# Arduino_MITCH_PCB.net
KiCad netlist of a schematic drawn in EAGLE
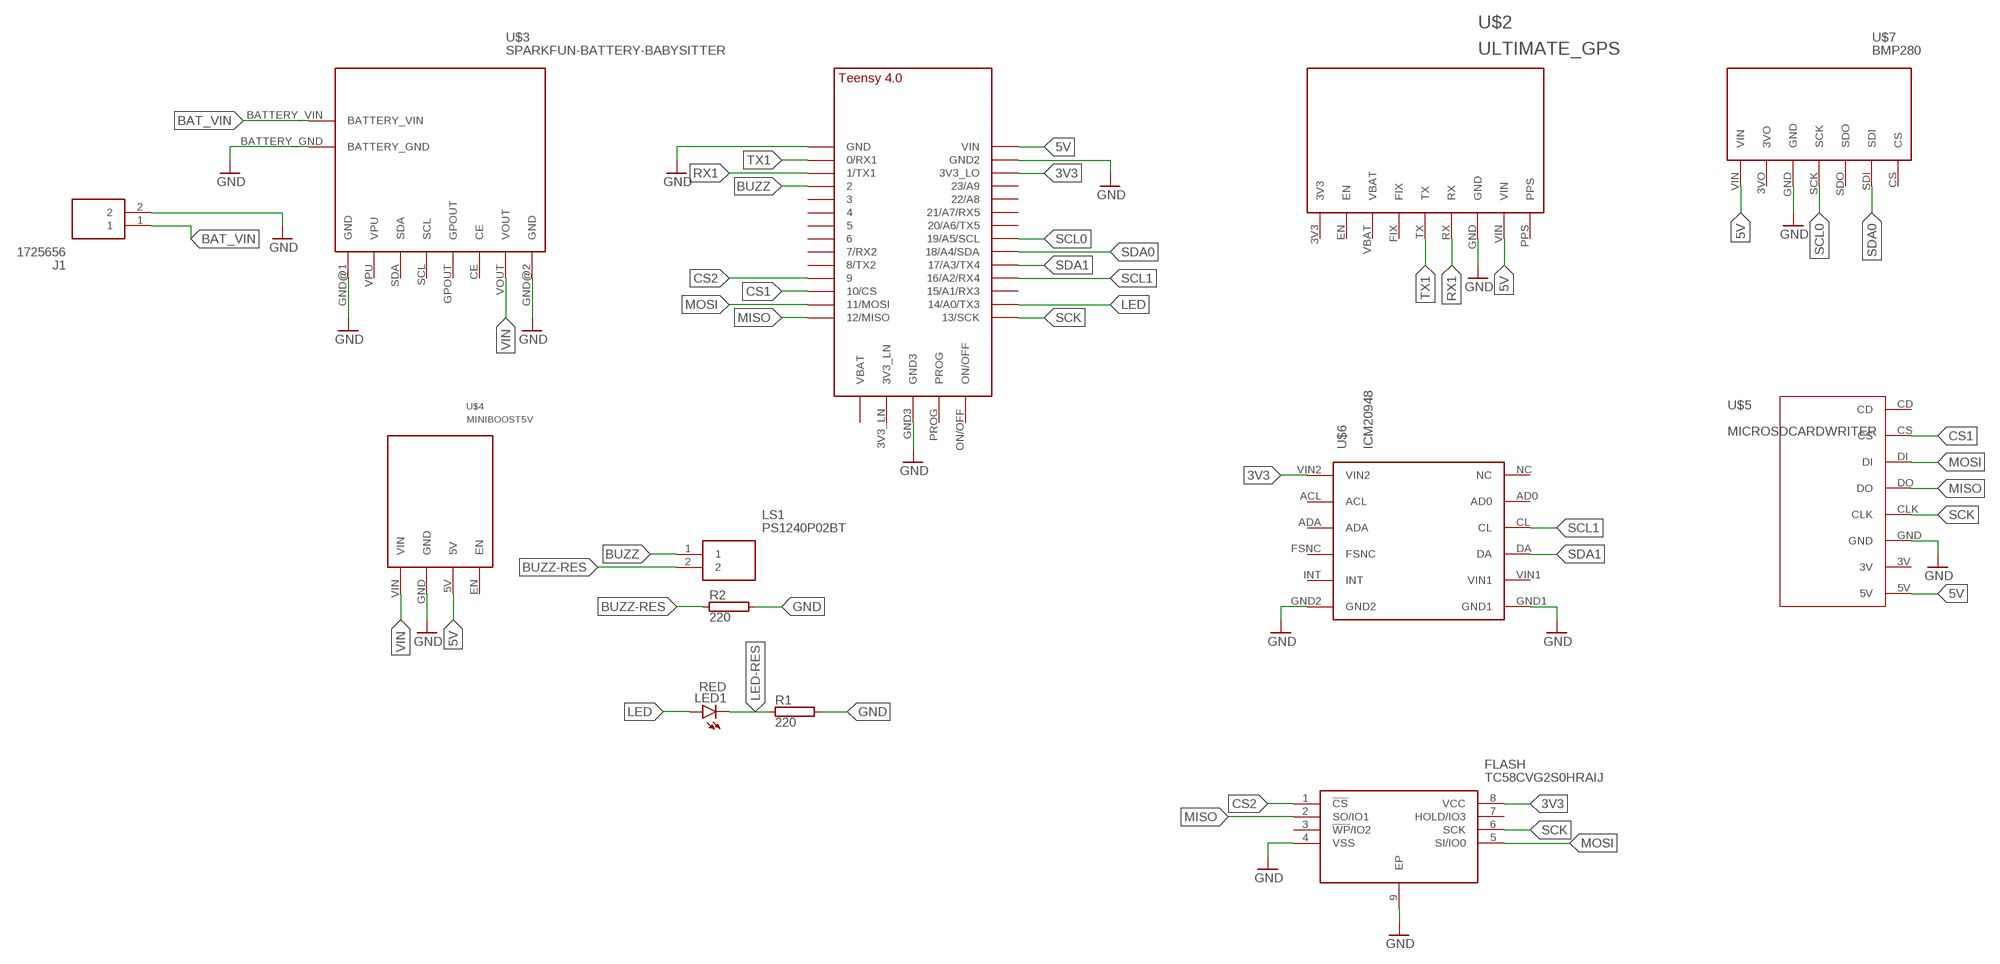
[diagram p0: schematic, sheet 1]

(export (version "E")
  (design (tool "Eeschema 10.0.6"))
  (components
    (comp (ref "FLASH")
      (value "TC58CVG2S0HRAIJ")
      (footprint "eagle-import:SON127P800X600X80-9N")
      (fields (field (name "MOUSER_PART_NUMBER") "757-TC58CVG2S0HRAIJ"))
      (libsource (lib "eagle-import") (part "TC58CVG2S0HRAIJ"))
    )
    (comp (ref "J1")
      (value "1725656")
      (footprint "eagle-import:1725656")
      (fields (field (name "MOUSER_PART_NUMBER") "651-1725656"))
      (libsource (lib "eagle-import") (part "1725656"))
    )
    (comp (ref "LED1")
      (value "RED")
      (footprint "eagle-import:LED5MM")
      (libsource (lib "eagle-import") (part "LED5MM"))
    )
    (comp (ref "LS1")
      (value "PS1240P02BT")
      (footprint "eagle-import:PS1240P02BT")
      (fields (field (name "MOUSER_PART_NUMBER") "810-PS1240P02BT"))
      (libsource (lib "eagle-import") (part "PS1240P02BT"))
    )
    (comp (ref "R1")
      (value "220")
      (footprint "eagle-import:HPS58")
      (libsource (lib "eagle-import") (part "RHPS58"))
    )
    (comp (ref "R2")
      (value "220")
      (footprint "eagle-import:HPS58")
      (libsource (lib "eagle-import") (part "RHPS58"))
    )
    (comp (ref "U$1")
      (value "TEENSY_4.0-BASIC")
      (footprint "eagle-import:TEENSY_4.0-BASIC")
      (libsource (lib "eagle-import") (part "TEENSY_4.0-BASIC"))
    )
    (comp (ref "U$2")
      (value "ULTIMATE_GPS")
      (footprint "eagle-import:ULTIMATE_GPS")
      (libsource (lib "eagle-import") (part "ULTIMATE_GPS"))
    )
    (comp (ref "U$3")
      (value "SPARKFUN-BATTERY-BABYSITTER")
      (footprint "eagle-import:SPARKFUN-BATTERY-BABYSITTER")
      (libsource (lib "eagle-import") (part "SPARKFUN-BATTERY-BABYSITTER"))
    )
    (comp (ref "U$4")
      (value "MINIBOOST5V")
      (footprint "eagle-import:MINIBOOST5V")
      (libsource (lib "eagle-import") (part "MINIBOOST5V"))
    )
    (comp (ref "U$5")
      (value "MICROSDCARDWRITER")
      (footprint "eagle-import:MICROSDCARDWRITER")
      (libsource (lib "eagle-import") (part "MICROSDCARDWRITER"))
    )
    (comp (ref "U$6")
      (value "ICM20948")
      (footprint "eagle-import:ICM20948")
      (libsource (lib "eagle-import") (part "ICM20948"))
    )
    (comp (ref "U$7")
      (value "BMP280")
      (footprint "eagle-import:BMP280")
      (libsource (lib "eagle-import") (part "BMP280"))
    )
  )
  (nets
    (net (code "1") (name "3V3") (class "Default")
      (node (ref "FLASH") (pin "8") (pinfunction "VCC_8") (pintype "bidirectional"))
      (node (ref "U$1") (pin "3V3_LO") (pinfunction "3V3_LO_3V3_LO") (pintype "bidirectional"))
      (node (ref "U$6") (pin "VIN2") (pinfunction "VIN2_VIN2") (pintype "bidirectional"))
    )
    (net (code "2") (name "5V") (class "Default")
      (node (ref "U$1") (pin "VIN") (pinfunction "VIN_VIN") (pintype "bidirectional"))
      (node (ref "U$2") (pin "VIN") (pinfunction "VIN_VIN") (pintype "bidirectional"))
      (node (ref "U$4") (pin "5V") (pinfunction "5V_5V") (pintype "bidirectional"))
      (node (ref "U$5") (pin "5V") (pinfunction "5V_5V") (pintype "bidirectional"))
      (node (ref "U$7") (pin "VIN") (pinfunction "VIN_VIN") (pintype "bidirectional"))
    )
    (net (code "3") (name "BAT_VIN") (class "Default")
      (node (ref "J1") (pin "1") (pinfunction "1_1") (pintype "bidirectional"))
      (node (ref "U$3") (pin "BATTERY_VIN") (pinfunction "BATTERY_VIN_BATTERY_VIN") (pintype "bidirectional"))
    )
    (net (code "4") (name "BUZZ") (class "Default")
      (node (ref "LS1") (pin "1") (pinfunction "1_1") (pintype "bidirectional"))
      (node (ref "U$1") (pin "2") (pinfunction "2_2") (pintype "bidirectional"))
    )
    (net (code "5") (name "BUZZ-RES") (class "Default")
      (node (ref "LS1") (pin "2") (pinfunction "2_2") (pintype "bidirectional"))
      (node (ref "R2") (pin "1") (pinfunction "1_1") (pintype "passive"))
    )
    (net (code "6") (name "CS1") (class "Default")
      (node (ref "U$1") (pin "10/CS") (pinfunction "10/CS_10/CS") (pintype "bidirectional"))
      (node (ref "U$5") (pin "CS") (pinfunction "CS_CS") (pintype "bidirectional"))
    )
    (net (code "7") (name "CS2") (class "Default")
      (node (ref "FLASH") (pin "1") (pinfunction "~{CS}_1") (pintype "bidirectional"))
      (node (ref "U$1") (pin "9/CS") (pinfunction "9_9/CS") (pintype "bidirectional"))
    )
    (net (code "8") (name "GND") (class "Default")
      (node (ref "FLASH") (pin "4") (pinfunction "VSS_4") (pintype "bidirectional"))
      (node (ref "FLASH") (pin "9") (pinfunction "EP_9") (pintype "bidirectional"))
      (node (ref "J1") (pin "2") (pinfunction "2_2") (pintype "bidirectional"))
      (node (ref "R1") (pin "2") (pinfunction "2_2") (pintype "passive"))
      (node (ref "R2") (pin "2") (pinfunction "2_2") (pintype "passive"))
      (node (ref "U$1") (pin "GND") (pinfunction "GND_GND") (pintype "bidirectional"))
      (node (ref "U$1") (pin "GND2") (pinfunction "GND2_GND2") (pintype "bidirectional"))
      (node (ref "U$1") (pin "GND3") (pinfunction "GND3_GND3") (pintype "bidirectional"))
      (node (ref "U$2") (pin "GND") (pinfunction "GND_GND") (pintype "bidirectional"))
      (node (ref "U$3") (pin "BATTERY_GND") (pinfunction "BATTERY_GND_BATTERY_GND") (pintype "bidirectional"))
      (node (ref "U$3") (pin "GND@1") (pinfunction "GND_GND@1") (pintype "bidirectional"))
      (node (ref "U$3") (pin "GND@2") (pinfunction "GND_GND@2") (pintype "bidirectional"))
      (node (ref "U$4") (pin "GND") (pinfunction "GND_GND") (pintype "bidirectional"))
      (node (ref "U$5") (pin "GND") (pinfunction "GND_GND") (pintype "bidirectional"))
      (node (ref "U$6") (pin "GND1") (pinfunction "GND1_GND1") (pintype "bidirectional"))
      (node (ref "U$6") (pin "GND2") (pinfunction "GND2_GND2") (pintype "bidirectional"))
      (node (ref "U$7") (pin "GND") (pinfunction "GND_GND") (pintype "bidirectional"))
    )
    (net (code "9") (name "LED") (class "Default")
      (node (ref "LED1") (pin "A") (pinfunction "A_A") (pintype "passive"))
      (node (ref "U$1") (pin "14/A0") (pinfunction "14/A0/TX3_14/A0") (pintype "bidirectional"))
    )
    (net (code "10") (name "LED-RES") (class "Default")
      (node (ref "LED1") (pin "K") (pinfunction "C_K") (pintype "passive"))
      (node (ref "R1") (pin "1") (pinfunction "1_1") (pintype "passive"))
    )
    (net (code "11") (name "MISO") (class "Default")
      (node (ref "FLASH") (pin "2") (pinfunction "SO/IO1_2") (pintype "bidirectional"))
      (node (ref "U$1") (pin "12/MISO") (pinfunction "12/MISO_12/MISO") (pintype "bidirectional"))
      (node (ref "U$5") (pin "DO") (pinfunction "DO_DO") (pintype "bidirectional"))
    )
    (net (code "12") (name "MOSI") (class "Default")
      (node (ref "FLASH") (pin "5") (pinfunction "SI/IO0_5") (pintype "bidirectional"))
      (node (ref "U$1") (pin "11/MOSI") (pinfunction "11/MOSI_11/MOSI") (pintype "bidirectional"))
      (node (ref "U$5") (pin "DI") (pinfunction "DI_DI") (pintype "bidirectional"))
    )
    (net (code "13") (name "RX1") (class "Default")
      (node (ref "U$1") (pin "1/TX") (pinfunction "1/TX1_1/TX") (pintype "bidirectional"))
      (node (ref "U$2") (pin "RX") (pinfunction "RX_RX") (pintype "bidirectional"))
    )
    (net (code "14") (name "SCK") (class "Default")
      (node (ref "FLASH") (pin "6") (pinfunction "SCK_6") (pintype "bidirectional"))
      (node (ref "U$1") (pin "13/SCK") (pinfunction "13/SCK_13/SCK") (pintype "bidirectional"))
      (node (ref "U$5") (pin "CLK") (pinfunction "CLK_CLK") (pintype "bidirectional"))
    )
    (net (code "15") (name "SCL0") (class "Default")
      (node (ref "U$1") (pin "19/A5/SCL") (pinfunction "19/A5/SCL_19/A5/SCL") (pintype "bidirectional"))
      (node (ref "U$7") (pin "SCK") (pinfunction "SCK_SCK") (pintype "bidirectional"))
    )
    (net (code "16") (name "SCL1") (class "Default")
      (node (ref "U$1") (pin "16/A2") (pinfunction "16/A2/RX4_16/A2") (pintype "bidirectional"))
      (node (ref "U$6") (pin "CL") (pinfunction "CL_CL") (pintype "bidirectional"))
    )
    (net (code "17") (name "SDA0") (class "Default")
      (node (ref "U$1") (pin "18/A4/SDA") (pinfunction "18/A4/SDA_18/A4/SDA") (pintype "bidirectional"))
      (node (ref "U$7") (pin "SDI") (pinfunction "SDI_SDI") (pintype "bidirectional"))
    )
    (net (code "18") (name "SDA1") (class "Default")
      (node (ref "U$1") (pin "17/A3") (pinfunction "17/A3/TX4_17/A3") (pintype "bidirectional"))
      (node (ref "U$6") (pin "DA") (pinfunction "DA_DA") (pintype "bidirectional"))
    )
    (net (code "19") (name "TX1") (class "Default")
      (node (ref "U$1") (pin "0/RX") (pinfunction "0/RX1_0/RX") (pintype "bidirectional"))
      (node (ref "U$2") (pin "TX") (pinfunction "TX_TX") (pintype "bidirectional"))
    )
    (net (code "20") (name "VIN") (class "Default")
      (node (ref "U$3") (pin "VOUT") (pinfunction "VOUT_VOUT") (pintype "bidirectional"))
      (node (ref "U$4") (pin "VIN") (pinfunction "VIN_VIN") (pintype "bidirectional"))
    )
    (net (code "21") (name "unconnected-(FLASH-HOLD{slash}IO3-Pad7)") (class "Default")
      (node (ref "FLASH") (pin "7") (pinfunction "HOLD/IO3_7") (pintype "bidirectional"))
    )
    (net (code "22") (name "unconnected-(FLASH-~{WP}{slash}IO2-Pad3)") (class "Default")
      (node (ref "FLASH") (pin "3") (pinfunction "~{WP}/IO2_3") (pintype "bidirectional"))
    )
    (net (code "23") (name "unconnected-(U$1-3-Pad3{slash}CANTX)") (class "Default")
      (node (ref "U$1") (pin "3/CANTX") (pinfunction "3_3/CANTX") (pintype "bidirectional"))
    )
    (net (code "24") (name "unconnected-(U$1-4-Pad4{slash}CANRX)") (class "Default")
      (node (ref "U$1") (pin "4/CANRX") (pinfunction "4_4/CANRX") (pintype "bidirectional"))
    )
    (net (code "25") (name "unconnected-(U$1-7{slash}RX2-Pad7)") (class "Default")
      (node (ref "U$1") (pin "7") (pinfunction "7/RX2_7") (pintype "bidirectional"))
    )
    (net (code "26") (name "unconnected-(U$1-8{slash}TX2-Pad8)") (class "Default")
      (node (ref "U$1") (pin "8") (pinfunction "8/TX2_8") (pintype "bidirectional"))
    )
    (net (code "27") (name "unconnected-(U$1-15{slash}A1{slash}RX3-Pad15{slash}A1)") (class "Default")
      (node (ref "U$1") (pin "15/A1") (pinfunction "15/A1/RX3_15/A1") (pintype "bidirectional"))
    )
    (net (code "28") (name "unconnected-(U$1-20{slash}A6{slash}TX5-Pad20{slash}A6)") (class "Default")
      (node (ref "U$1") (pin "20/A6") (pinfunction "20/A6/TX5_20/A6") (pintype "bidirectional"))
    )
    (net (code "29") (name "unconnected-(U$1-21{slash}A7{slash}RX5-Pad21{slash}A7)") (class "Default")
      (node (ref "U$1") (pin "21/A7") (pinfunction "21/A7/RX5_21/A7") (pintype "bidirectional"))
    )
    (net (code "30") (name "unconnected-(U$1-Pad3V3_LN)") (class "Default")
      (node (ref "U$1") (pin "3V3_LN") (pinfunction "3V3_LN_3V3_LN") (pintype "bidirectional"))
    )
    (net (code "31") (name "unconnected-(U$1-Pad5)") (class "Default")
      (node (ref "U$1") (pin "5") (pinfunction "5_5") (pintype "bidirectional"))
    )
    (net (code "32") (name "unconnected-(U$1-Pad6)") (class "Default")
      (node (ref "U$1") (pin "6") (pinfunction "6_6") (pintype "bidirectional"))
    )
    (net (code "33") (name "unconnected-(U$1-Pad22{slash}A8)") (class "Default")
      (node (ref "U$1") (pin "22/A8") (pinfunction "22/A8_22/A8") (pintype "bidirectional"))
    )
    (net (code "34") (name "unconnected-(U$1-Pad23{slash}A9)") (class "Default")
      (node (ref "U$1") (pin "23/A9") (pinfunction "23/A9_23/A9") (pintype "bidirectional"))
    )
    (net (code "35") (name "unconnected-(U$1-PadON{slash}OFF)") (class "Default")
      (node (ref "U$1") (pin "ON/OFF") (pinfunction "ON/OFF_ON/OFF") (pintype "bidirectional"))
    )
    (net (code "36") (name "unconnected-(U$1-PadPROG)") (class "Default")
      (node (ref "U$1") (pin "PROG") (pinfunction "PROG_PROG") (pintype "bidirectional"))
    )
    (net (code "37") (name "unconnected-(U$1-VBAT-PadVBAT\\)") (class "Default")
      (node (ref "U$1") (pin "VBAT\\") (pinfunction "VBAT_VBAT\\") (pintype "bidirectional"))
    )
    (net (code "38") (name "unconnected-(U$2-Pad3V3)") (class "Default")
      (node (ref "U$2") (pin "3V3") (pinfunction "3V3_3V3") (pintype "bidirectional"))
    )
    (net (code "39") (name "unconnected-(U$2-PadEN)") (class "Default")
      (node (ref "U$2") (pin "EN") (pinfunction "EN_EN") (pintype "bidirectional"))
    )
    (net (code "40") (name "unconnected-(U$2-PadFIX)") (class "Default")
      (node (ref "U$2") (pin "FIX") (pinfunction "FIX_FIX") (pintype "bidirectional"))
    )
    (net (code "41") (name "unconnected-(U$2-PadPPS)") (class "Default")
      (node (ref "U$2") (pin "PPS") (pinfunction "PPS_PPS") (pintype "bidirectional"))
    )
    (net (code "42") (name "unconnected-(U$2-PadVBAT)") (class "Default")
      (node (ref "U$2") (pin "VBAT") (pinfunction "VBAT_VBAT") (pintype "bidirectional"))
    )
    (net (code "43") (name "unconnected-(U$3-PadCE)") (class "Default")
      (node (ref "U$3") (pin "CE") (pinfunction "CE_CE") (pintype "bidirectional"))
    )
    (net (code "44") (name "unconnected-(U$3-PadGPOUT)") (class "Default")
      (node (ref "U$3") (pin "GPOUT") (pinfunction "GPOUT_GPOUT") (pintype "bidirectional"))
    )
    (net (code "45") (name "unconnected-(U$3-PadSCL)") (class "Default")
      (node (ref "U$3") (pin "SCL") (pinfunction "SCL_SCL") (pintype "bidirectional"))
    )
    (net (code "46") (name "unconnected-(U$3-PadSDA)") (class "Default")
      (node (ref "U$3") (pin "SDA") (pinfunction "SDA_SDA") (pintype "bidirectional"))
    )
    (net (code "47") (name "unconnected-(U$3-PadVPU)") (class "Default")
      (node (ref "U$3") (pin "VPU") (pinfunction "VPU_VPU") (pintype "bidirectional"))
    )
    (net (code "48") (name "unconnected-(U$4-PadEN)") (class "Default")
      (node (ref "U$4") (pin "EN") (pinfunction "EN_EN") (pintype "bidirectional"))
    )
    (net (code "49") (name "unconnected-(U$5-Pad3V)") (class "Default")
      (node (ref "U$5") (pin "3V") (pinfunction "3V_3V") (pintype "bidirectional"))
    )
    (net (code "50") (name "unconnected-(U$5-PadCD)") (class "Default")
      (node (ref "U$5") (pin "CD") (pinfunction "CD_CD") (pintype "bidirectional"))
    )
    (net (code "51") (name "unconnected-(U$6-PadACL)") (class "Default")
      (node (ref "U$6") (pin "ACL") (pinfunction "ACL_ACL") (pintype "bidirectional"))
    )
    (net (code "52") (name "unconnected-(U$6-PadAD0)") (class "Default")
      (node (ref "U$6") (pin "AD0") (pinfunction "AD0_AD0") (pintype "bidirectional"))
    )
    (net (code "53") (name "unconnected-(U$6-PadADA)") (class "Default")
      (node (ref "U$6") (pin "ADA") (pinfunction "ADA_ADA") (pintype "bidirectional"))
    )
    (net (code "54") (name "unconnected-(U$6-PadFSNC)") (class "Default")
      (node (ref "U$6") (pin "FSNC") (pinfunction "FSNC_FSNC") (pintype "bidirectional"))
    )
    (net (code "55") (name "unconnected-(U$6-PadINT)") (class "Default")
      (node (ref "U$6") (pin "INT") (pinfunction "INT_INT") (pintype "bidirectional"))
    )
    (net (code "56") (name "unconnected-(U$6-PadNC)") (class "Default")
      (node (ref "U$6") (pin "NC") (pinfunction "NC_NC") (pintype "bidirectional"))
    )
    (net (code "57") (name "unconnected-(U$6-PadVIN1)") (class "Default")
      (node (ref "U$6") (pin "VIN1") (pinfunction "VIN1_VIN1") (pintype "bidirectional"))
    )
    (net (code "58") (name "unconnected-(U$7-Pad3VO)") (class "Default")
      (node (ref "U$7") (pin "3VO") (pinfunction "3VO_3VO") (pintype "bidirectional"))
    )
    (net (code "59") (name "unconnected-(U$7-PadCS)") (class "Default")
      (node (ref "U$7") (pin "CS") (pinfunction "CS_CS") (pintype "bidirectional"))
    )
    (net (code "60") (name "unconnected-(U$7-PadSDO)") (class "Default")
      (node (ref "U$7") (pin "SDO") (pinfunction "SDO_SDO") (pintype "bidirectional"))
    )
  )
)
